# MPU6050.net
KiCad netlist of a schematic drawn in Altium Designer
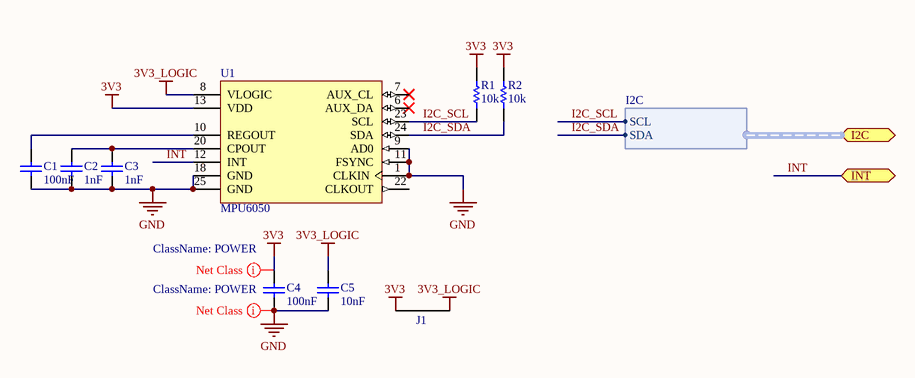
[diagram p0: MPU6050.SchDoc]

(export (version "E")
  (design (tool "Eeschema 10.0.6"))
  (components
    (comp (ref "C1")
      (value "100nF")
      (footprint "agh_racing_2018:CAP_0603_IPC_MD")
      (description "Capacitor")
      (fields (field (name "Comment") "Cap"))
      (libsource (lib "agh_racing_2018") (part "Cap"))
    )
    (comp (ref "C2")
      (value "1nF")
      (footprint "agh_racing_2018:CAP_0603_IPC_MD")
      (description "Capacitor")
      (fields (field (name "Comment") "Cap"))
      (libsource (lib "agh_racing_2018") (part "Cap"))
    )
    (comp (ref "C3")
      (value "1nF")
      (footprint "agh_racing_2018:CAP_0603_IPC_MD")
      (description "Capacitor")
      (fields (field (name "Comment") "Cap"))
      (libsource (lib "agh_racing_2018") (part "Cap"))
    )
    (comp (ref "C4")
      (value "100nF")
      (footprint "agh_racing_2018:CAP_0603_IPC_MD")
      (description "Capacitor")
      (fields (field (name "Comment") "Cap"))
      (libsource (lib "agh_racing_2018") (part "Cap"))
    )
    (comp (ref "C5")
      (value "10nF")
      (footprint "agh_racing_2018:CAP_0603_IPC_MD")
      (description "Capacitor")
      (fields (field (name "Comment") "Cap"))
      (libsource (lib "agh_racing_2018") (part "Cap"))
    )
    (comp (ref "J1")
      (value "NetTie")
      (footprint "NETTIE")
      (libsource (lib "agh_racing_2018") (part "NetTie"))
    )
    (comp (ref "R1")
      (value "10k")
      (footprint "agh_racing_2018:RES_0603_IPC_HD")
      (description "Resistor")
      (fields (field (name "Comment") "Res"))
      (libsource (lib "agh_racing_2018") (part "Res"))
    )
    (comp (ref "R2")
      (value "10k")
      (footprint "agh_racing_2018:RES_0603_IPC_HD")
      (description "Resistor")
      (fields (field (name "Comment") "Res"))
      (libsource (lib "agh_racing_2018") (part "Res"))
    )
    (comp (ref "U1")
      (value "MPU6050")
      (footprint "QFN24_IPC_MD")
      (description "3 axis accelerometer and gyroscope")
      (fields (field (name "MANUFACTURER") "Invensense") (field (name "MANUFACTURER PART NUMBER") "MPU-6050"))
      (libsource (lib "agh_racing_2018") (part "MPU6050"))
    )
  )
  (nets
    (net (code "2") (name "/I2C_SCL") (class "Default")
      (node (ref "R1") (pin "1") (pinfunction "1_1") (pintype "passive"))
      (node (ref "U1") (pin "23") (pinfunction "SCL_23") (pintype "bidirectional"))
    )
    (net (code "3") (name "/I2C_SDA") (class "Default")
      (node (ref "R2") (pin "1") (pinfunction "1_1") (pintype "passive"))
      (node (ref "U1") (pin "24") (pinfunction "SDA_24") (pintype "bidirectional"))
    )
    (net (code "4") (name "/INT") (class "Default")
      (node (ref "U1") (pin "12") (pinfunction "INT_12") (pintype "open_collector"))
    )
    (net (code "6") (name "3V3") (class "Default")
      (node (ref "C4") (pin "2") (pinfunction "2_2") (pintype "passive"))
      (node (ref "J1") (pin "1") (pinfunction "1_1") (pintype "passive"))
      (node (ref "R1") (pin "2") (pinfunction "2_2") (pintype "passive"))
      (node (ref "R2") (pin "2") (pinfunction "2_2") (pintype "passive"))
      (node (ref "U1") (pin "13") (pinfunction "VDD_13") (pintype "power_in"))
    )
    (net (code "7") (name "3V3_LOGIC") (class "Default")
      (node (ref "C5") (pin "2") (pinfunction "2_2") (pintype "passive"))
      (node (ref "J1") (pin "2") (pinfunction "2_2") (pintype "passive"))
      (node (ref "U1") (pin "8") (pinfunction "VLOGIC_8") (pintype "power_in"))
    )
    (net (code "8") (name "GND") (class "Default")
      (node (ref "C1") (pin "1") (pinfunction "1_1") (pintype "passive"))
      (node (ref "C2") (pin "1") (pinfunction "1_1") (pintype "passive"))
      (node (ref "C3") (pin "1") (pinfunction "1_1") (pintype "passive"))
      (node (ref "C4") (pin "1") (pinfunction "1_1") (pintype "passive"))
      (node (ref "C5") (pin "1") (pinfunction "1_1") (pintype "passive"))
      (node (ref "U1") (pin "1") (pinfunction "CLKIN_1") (pintype "passive"))
      (node (ref "U1") (pin "11") (pinfunction "FSYNC_11") (pintype "input"))
      (node (ref "U1") (pin "18") (pinfunction "GND_18") (pintype "power_in"))
      (node (ref "U1") (pin "25") (pinfunction "GND_25") (pintype "power_in"))
      (node (ref "U1") (pin "9") (pinfunction "AD0_9") (pintype "input"))
    )
    (net (code "9") (name "Net-(U1-CPOUT)") (class "Default")
      (node (ref "C2") (pin "2") (pinfunction "2_2") (pintype "passive"))
      (node (ref "C3") (pin "2") (pinfunction "2_2") (pintype "passive"))
      (node (ref "U1") (pin "20") (pinfunction "CPOUT_20") (pintype "passive"))
    )
    (net (code "10") (name "Net-(U1-REGOUT)") (class "Default")
      (node (ref "C1") (pin "2") (pinfunction "2_2") (pintype "passive"))
      (node (ref "U1") (pin "10") (pinfunction "REGOUT_10") (pintype "passive"))
    )
    (net (code "11") (name "unconnected-(U1-AUX_CL-Pad7)") (class "Default")
      (node (ref "U1") (pin "7") (pinfunction "AUX_CL_7") (pintype "bidirectional+no_connect"))
    )
    (net (code "12") (name "unconnected-(U1-AUX_DA-Pad6)") (class "Default")
      (node (ref "U1") (pin "6") (pinfunction "AUX_DA_6") (pintype "bidirectional+no_connect"))
    )
    (net (code "13") (name "unconnected-(U1-CLKOUT-Pad22)") (class "Default")
      (node (ref "U1") (pin "22") (pinfunction "CLKOUT_22") (pintype "output"))
    )
    (net (code "14") (name "unconnected-(U1-RESV-Pad19)") (class "Default")
      (node (ref "U1") (pin "19") (pinfunction "RESV_19") (pintype "passive"))
    )
    (net (code "15") (name "unconnected-(U1-RESV-Pad21)") (class "Default")
      (node (ref "U1") (pin "21") (pinfunction "RESV_21") (pintype "passive"))
    )
  )
)
